# firestarter.net
KiCad netlist of a schematic drawn in EAGLE
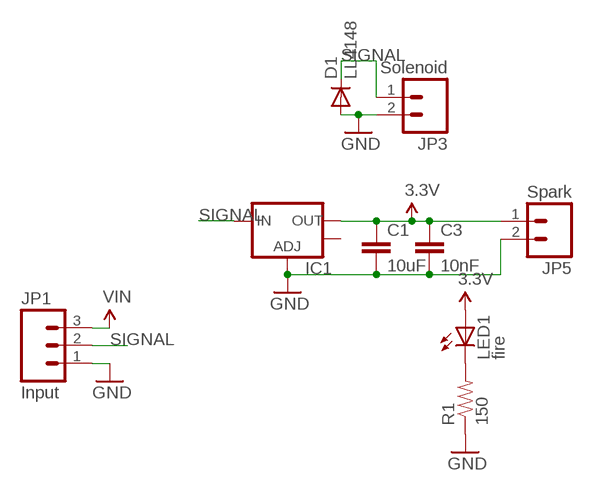
[diagram p0: schematic, sheet 1]

(export (version "E")
  (design (tool "Eeschema 10.0.6"))
  (components
    (comp (ref "C1")
      (value "10uF")
      (footprint "eagle-import:0603-CAP")
      (libsource (lib "eagle-import") (part "CAP0603-CAP"))
    )
    (comp (ref "C3")
      (value "10nF")
      (footprint "eagle-import:0603-CAP")
      (libsource (lib "eagle-import") (part "CAP0603-CAP"))
    )
    (comp (ref "D1")
      (value "LL4148")
      (footprint "eagle-import:MLL34")
      (libsource (lib "eagle-import") (part "LL4148"))
    )
    (comp (ref "IC1")
      (value "V_REG_LM1117SOT223")
      (footprint "eagle-import:SOT223")
      (libsource (lib "eagle-import") (part "V_REG_LM1117SOT223"))
    )
    (comp (ref "JP1")
      (value "Input")
      (footprint "eagle-import:MOLEX-1X3_LOCK")
      (libsource (lib "eagle-import") (part "M03POLAR_LOCK"))
    )
    (comp (ref "JP3")
      (value "Solenoid")
      (footprint "eagle-import:MOLEX-1X2_LOCK")
      (libsource (lib "eagle-import") (part "M02POLAR_LOCK"))
    )
    (comp (ref "JP5")
      (value "Spark")
      (footprint "eagle-import:MOLEX-1X2_LOCK")
      (libsource (lib "eagle-import") (part "M02POLAR_LOCK"))
    )
    (comp (ref "LED1")
      (value "fire")
      (footprint "eagle-import:LED-0603")
      (libsource (lib "eagle-import") (part "LED0603"))
    )
    (comp (ref "R1")
      (value "150")
      (footprint "eagle-import:0603-RES")
      (libsource (lib "eagle-import") (part "RESISTOR0603-RES"))
    )
  )
  (nets
    (net (code "1") (name "/SIGNAL") (class "Default")
      (node (ref "D1") (pin "C") (pinfunction "C_C") (pintype "passive"))
      (node (ref "IC1") (pin "3") (pinfunction "IN_3") (pintype "input"))
      (node (ref "JP1") (pin "2") (pinfunction "2_2") (pintype "passive"))
      (node (ref "JP3") (pin "1") (pinfunction "1_1") (pintype "passive"))
    )
    (net (code "2") (name "3.3V") (class "Default")
      (node (ref "C1") (pin "1") (pinfunction "1_1") (pintype "passive"))
      (node (ref "C3") (pin "1") (pinfunction "1_1") (pintype "passive"))
      (node (ref "IC1") (pin "2") (pinfunction "OUT_2") (pintype "output"))
      (node (ref "JP5") (pin "1") (pinfunction "1_1") (pintype "passive"))
      (node (ref "LED1") (pin "A") (pinfunction "A_A") (pintype "passive"))
    )
    (net (code "3") (name "GND") (class "Default")
      (node (ref "C1") (pin "2") (pinfunction "2_2") (pintype "passive"))
      (node (ref "C3") (pin "2") (pinfunction "2_2") (pintype "passive"))
      (node (ref "D1") (pin "A") (pinfunction "A_A") (pintype "passive"))
      (node (ref "IC1") (pin "1") (pinfunction "ADJ_1") (pintype "input"))
      (node (ref "JP1") (pin "1") (pinfunction "1_1") (pintype "passive"))
      (node (ref "JP3") (pin "2") (pinfunction "2_2") (pintype "passive"))
      (node (ref "JP5") (pin "2") (pinfunction "2_2") (pintype "passive"))
      (node (ref "R1") (pin "1") (pinfunction "1_1") (pintype "passive"))
    )
    (net (code "4") (name "Net-(LED1-PadC)") (class "Default")
      (node (ref "LED1") (pin "C") (pinfunction "C_C") (pintype "passive"))
      (node (ref "R1") (pin "2") (pinfunction "2_2") (pintype "passive"))
    )
    (net (code "5") (name "VIN") (class "Default")
      (node (ref "JP1") (pin "3") (pinfunction "3_3") (pintype "passive"))
    )
    (net (code "6") (name "unconnected-(IC1-OUT-Pad4)") (class "Default")
      (node (ref "IC1") (pin "4") (pinfunction "OUT_4") (pintype "output"))
    )
  )
)
